# TB-S5D5_p02_Power-v1_2.net
KiCad netlist of a schematic drawn in Altium Designer
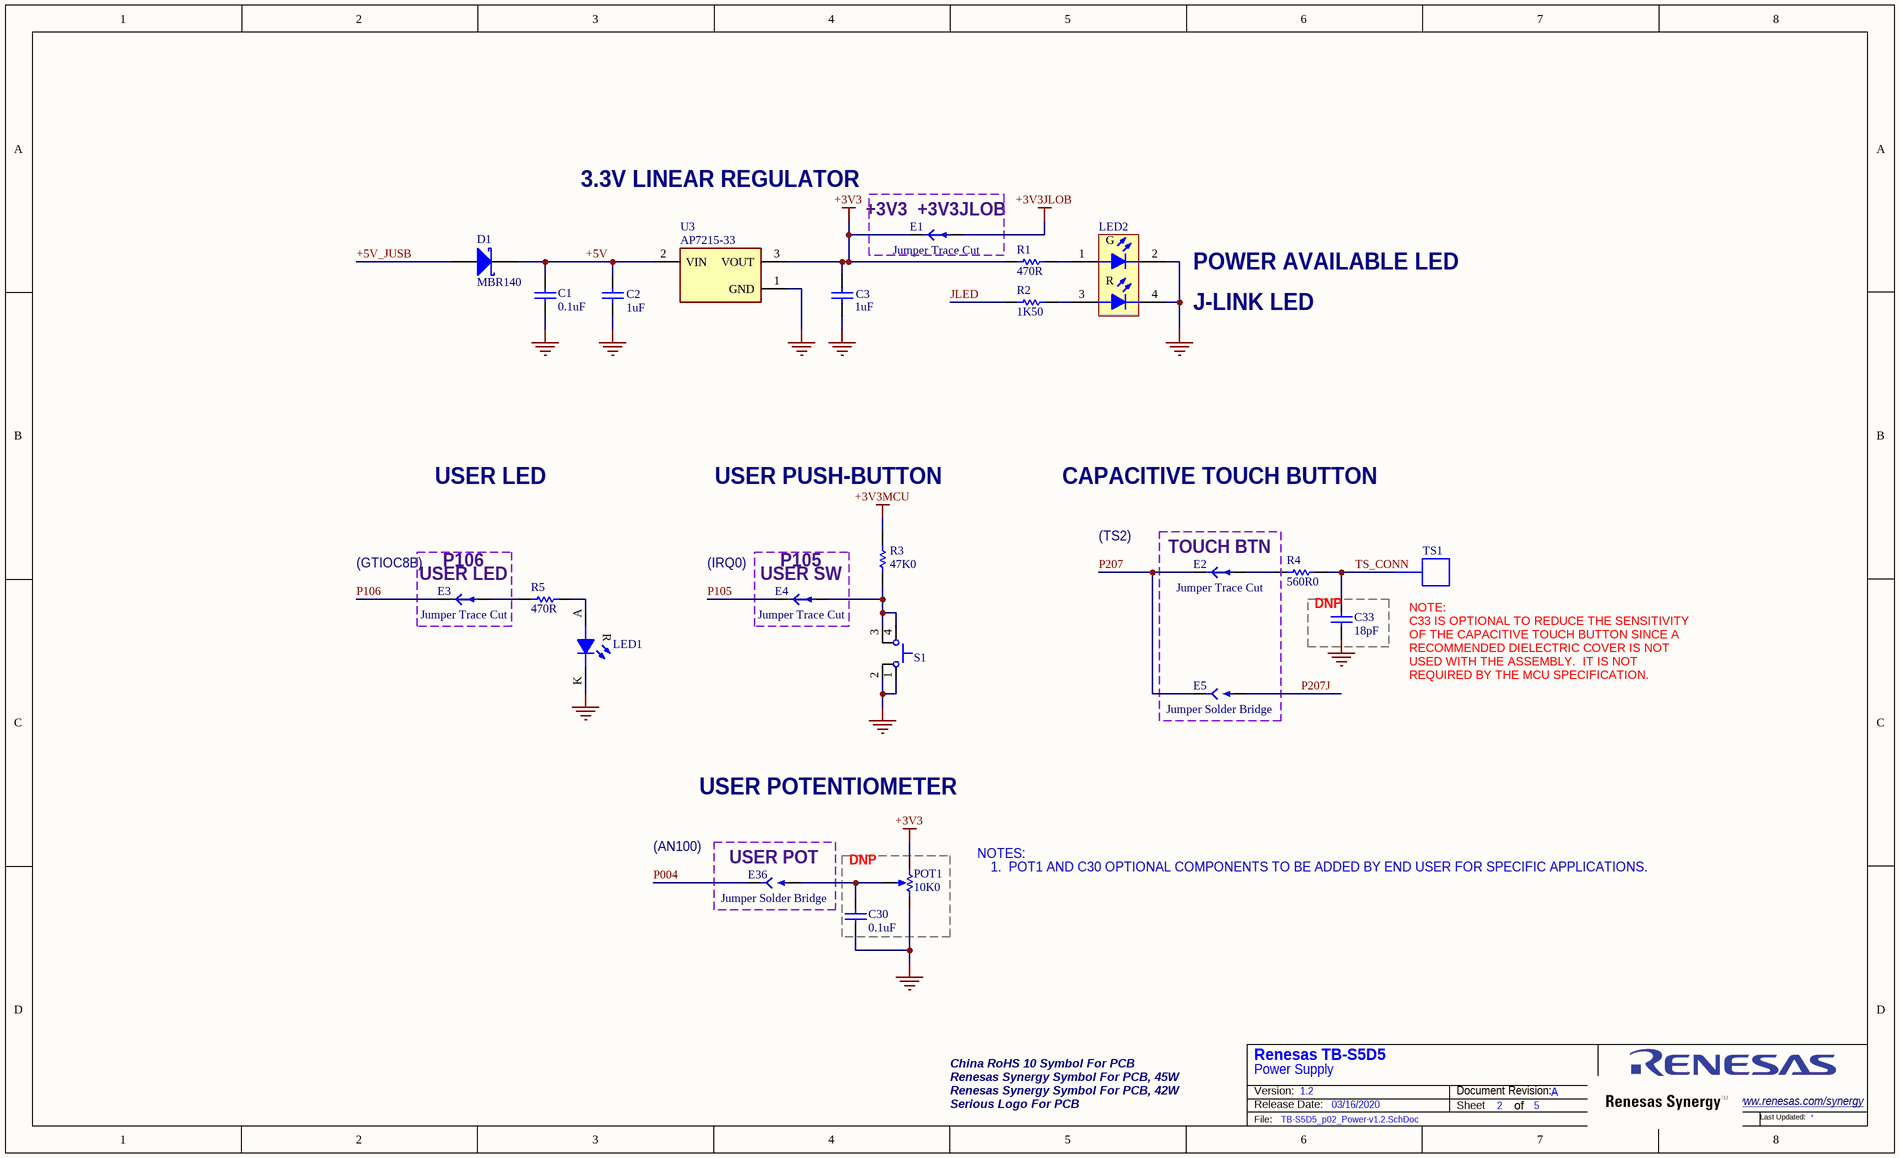
[diagram p0: TB-S5D5_p02_Power-v1.2.SchDoc]

(export (version "E")
  (design (tool "Eeschema 10.0.6"))
  (components
    (comp (ref "A_Logo1")
      (value "This BOM is for Engineering Use Only, NOT FOR PURCHASE USE.")
      (footprint "_SeriousEngineering")
      (description "Combination disclaimer and Serious Integrated Design splash")
      (fields (field (name "MFG PART NUMBER") "(none)"))
      (libsource (lib "SpecialPartsLib") (part "A_Serious_Engineering_Logo"))
    )
    (comp (ref "A_Symbol1")
      (value "This Symbol Placed on PCB only.")
      (footprint "ChinaRoHS-7mm")
      (description "China RoHs Symbol Circle-7")
      (libsource (lib "SpecialPartsLib") (part "A_Symbol_ChinaRoHS07"))
    )
    (comp (ref "A_Symbol2")
      (value "This Symbol Placed on PCB only.")
      (footprint "RenesasSynergyLogo45x7")
      (description "Renesas Synergy Logo, Std 45Wx7.4Hmm")
      (libsource (lib "SpecialPartsLib") (part "A_Symbol_RenesasSynergy-45x7"))
    )
    (comp (ref "A_Symbol3")
      (value "This Symbol Placed on PCB only.")
      (footprint "RenesasSynergyLogo42x7")
      (description "Renesas Synergy Logo, 42Wx6.8Hmm")
      (libsource (lib "SpecialPartsLib") (part "A_Symbol_RenesasSynergy-42x7"))
    )
    (comp (ref "C1")
      (value "CAP-000029-01")
      (footprint "CAPC0603-01")
      (description "Ceramic Chip Capacitor 0603 0.1uF 50V")
      (fields
        (field (name "MANUFACTURER") "Samsung")
        (field (name "MFG PART NUMBER") "CL10B104KB8NNNC")
        (field (name "CAPACITANCE") "0.1uF")
      )
      (libsource (lib "Capacitors") (part "CAP-000029-01"))
    )
    (comp (ref "C2")
      (value "CAP-000063-01")
      (footprint "CAPC0402-01")
      (description "Ceramic Chip Capacitor 0402 1uF 16V")
      (fields
        (field (name "MANUFACTURER") "Samsung")
        (field (name "MFG PART NUMBER") "CL05A105KO5NNNC")
        (field (name "CAPACITANCE") "1uF")
      )
      (libsource (lib "Capacitors") (part "CAP-000063-01"))
    )
    (comp (ref "C3")
      (value "CAP-000063-01")
      (footprint "CAPC0402-01")
      (description "Ceramic Chip Capacitor 0402 1uF 16V")
      (fields
        (field (name "MANUFACTURER") "Samsung")
        (field (name "MFG PART NUMBER") "CL05A105KO5NNNC")
        (field (name "CAPACITANCE") "1uF")
      )
      (libsource (lib "Capacitors") (part "CAP-000063-01"))
    )
    (comp (ref "C30")
      (value "CAP-000029-01")
      (footprint "CAPC0603-01")
      (description "Ceramic Chip Capacitor 0603 0.1uF 50V")
      (fields
        (field (name "MANUFACTURER") "Samsung")
        (field (name "MFG PART NUMBER") "CL10B104KB8NNNC")
        (field (name "CAPACITANCE") "0.1uF")
      )
      (libsource (lib "Capacitors") (part "CAP-000029-01"))
    )
    (comp (ref "C33")
      (value "CAP-000040-01")
      (footprint "CAPC0603-01")
      (description "Ceramic Chip Capacitor 0603 18pF 50V")
      (fields
        (field (name "MANUFACTURER") "Samsung")
        (field (name "MFG PART NUMBER") "CL10C180JB8NNNC")
        (field (name "CAPACITANCE") "18pF")
      )
      (libsource (lib "Capacitors") (part "CAP-000040-01"))
    )
    (comp (ref "D1")
      (value "DIO-000012-01")
      (footprint "ONSEMI_SOD-123LF")
      (description "OnSemi Schottky Power Rectifier 40V 1A")
      (fields
        (field (name "MANUFACTURER") "OnSemi")
        (field (name "VOLTAGE") "40V")
        (field (name "DISPLAY NAME") "MBR140")
      )
      (libsource (lib "Semiconductors") (part "DIO-000012-01"))
    )
    (comp (ref "E1")
      (value "Jumper Trace Cut")
      (footprint "E_PadsTraceCut0805")
      (description "Pads on PCB with Trace Between for Cutting to isolate")
      (libsource (lib "TB_SpecialLib") (part "E_JmpTraceCut"))
    )
    (comp (ref "E2")
      (value "Jumper Trace Cut")
      (footprint "E_PadsTraceCut0805")
      (description "Pads on PCB with Trace Between for Cutting to isolate")
      (libsource (lib "TB_SpecialLib") (part "E_JmpTraceCut"))
    )
    (comp (ref "E3")
      (value "Jumper Trace Cut")
      (footprint "E_PadsTraceCut0805")
      (description "Pads on PCB with Trace Between for Cutting to isolate")
      (libsource (lib "TB_SpecialLib") (part "E_JmpTraceCut"))
    )
    (comp (ref "E4")
      (value "Jumper Trace Cut")
      (footprint "E_PadsTraceCut0805")
      (description "Pads on PCB with Trace Between for Cutting to isolate")
      (libsource (lib "TB_SpecialLib") (part "E_JmpTraceCut"))
    )
    (comp (ref "E5")
      (value "Jumper Solder Bridge")
      (footprint "E_PadsSplit0805")
      (description "Pads on PCB with Narrow Gap to allow Solder Bridging")
      (libsource (lib "TB_SpecialLib") (part "E_JmpSldrBridge"))
    )
    (comp (ref "E36")
      (value "Jumper Solder Bridge")
      (footprint "E_PadsSplit0805")
      (description "Pads on PCB with Narrow Gap to allow Solder Bridging")
      (libsource (lib "TB_SpecialLib") (part "E_JmpSldrBridge"))
    )
    (comp (ref "LED1")
      (value "LED-000005-01")
      (footprint "LED_0603-RED")
      (description "Lite-On LED Red Clear 0603")
      (fields (field (name "MANUFACTURER") "Lite-On") (field (name "MFG PART NUMBER") "LTST-C191KRKT"))
      (libsource (lib "Semiconductors") (part "LED-000005-01"))
    )
    (comp (ref "LED2")
      (value "LED-000001-01")
      (footprint "LED_DIALIGHT-598-8610")
      (description "Dialight Bicolor LED Red/Green 1210")
      (fields (field (name "MANUFACTURER") "Dialight") (field (name "MFG PART NUMBER") "598-8610-207F"))
      (libsource (lib "Semiconductors") (part "LED-000001-01"))
    )
    (comp (ref "POT1")
      (value "POT-000001-02")
      (footprint "BOURNS_3352T")
      (description "Bourns Single Turn Trimmer 10K0")
      (fields
        (field (name "MFG PART NUMBER") "3352T-1-103LF")
        (field (name "TOLERANCE") "20%")
        (field (name "RESISTANCE") "10K0")
      )
      (libsource (lib "Misc") (part "POT-000001-02"))
    )
    (comp (ref "R1")
      (value "RES-000124-01")
      (footprint "RESC0402-01")
      (description "Chip Resistor Thick Film 0402 470R 0.5% 1/16W")
      (fields
        (field (name "MANUFACTURER") "Panasonic")
        (field (name "MFG PART NUMBER") "ERA-2AED471X")
        (field (name "RESISTANCE") "470R")
      )
      (libsource (lib "Resistors") (part "RES-000124-01"))
    )
    (comp (ref "R2")
      (value "RES-000140-01")
      (footprint "RESC0402-01")
      (description "Chip Resistor Thick Film 0402 1K50 0.5% 1/16W")
      (fields
        (field (name "MANUFACTURER") "Panasonic")
        (field (name "MFG PART NUMBER") "ERA-2AED152X")
        (field (name "RESISTANCE") "1K50")
      )
      (libsource (lib "Resistors") (part "RES-000140-01"))
    )
    (comp (ref "R3")
      (value "RES-000173-01")
      (footprint "RESC0402-01")
      (description "Chip Resistor Thick Film 0402 47K0 1% 1/10W")
      (fields
        (field (name "MANUFACTURER") "Panasonic")
        (field (name "MFG PART NUMBER") "ERJ-2RKF4702X")
        (field (name "RESISTANCE") "47K0")
      )
      (libsource (lib "Resistors") (part "RES-000173-01"))
    )
    (comp (ref "R4")
      (value "RES-000206-01")
      (footprint "RESC0603-01")
      (description "Chip Resistor Thick Film 0603 560R0 1% 1/10W")
      (fields
        (field (name "MANUFACTURER") "Panasonic")
        (field (name "MFG PART NUMBER") "ERJ-3EKF5600V")
        (field (name "RESISTANCE") "560R0")
      )
      (libsource (lib "Resistors") (part "RES-000206-01"))
    )
    (comp (ref "R5")
      (value "RES-000124-01")
      (footprint "RESC0402-01")
      (description "Chip Resistor Thick Film 0402 470R 0.5% 1/16W")
      (fields
        (field (name "MANUFACTURER") "Panasonic")
        (field (name "MFG PART NUMBER") "ERA-2AED471X")
        (field (name "RESISTANCE") "470R")
      )
      (libsource (lib "Resistors") (part "RES-000124-01"))
    )
    (comp (ref "S1")
      (value "SWT-000013-01")
      (footprint "SW_C&K_PTS645_43")
      (description "Push Button Switch 6 x 6mm 4.3mm High")
      (fields (field (name "MANUFACTURER") "C&K") (field (name "MFG PART NUMBER") "PTS645SM43SMTR92 LFS"))
      (libsource (lib "Misc") (part "SWT-000013-01"))
    )
    (comp (ref "TS1")
      (value "TOUCH_PAD_OL")
      (footprint "RENESAS_TSP_OL")
      (description "Renesas Touch Sense Pad Outline (for non-Pad use)")
      (libsource (lib "SpecialPartsLib") (part "TOUCH_PAD_OL"))
    )
    (comp (ref "U3")
      (value "ICN-000215-01")
      (footprint "SOT-89-3")
      (description "LDO Regulator 3.3V 600mA")
      (fields
        (field (name "MANUFACTURER") "Diodes")
        (field (name "MFG PART NUMBER") "AP7215-33YG-13")
        (field (name "DISPLAY NAME") "AP7215-33")
      )
      (libsource (lib "IC_Power") (part "ICN-000215-01"))
    )
  )
  (nets
    (net (code "1") (name "+3V3") (class "Default")
      (node (ref "C3") (pin "2") (pinfunction "2_2") (pintype "passive"))
      (node (ref "E1") (pin "1") (pinfunction "A_1") (pintype "passive"))
      (node (ref "POT1") (pin "1") (pinfunction "1_1") (pintype "passive"))
      (node (ref "R1") (pin "1") (pinfunction "1_1") (pintype "passive"))
      (node (ref "U3") (pin "3") (pinfunction "VOUT_3") (pintype "power_in"))
    )
    (net (code "2") (name "+3V3JLOB") (class "Default")
      (node (ref "E1") (pin "2") (pinfunction "A_2") (pintype "passive"))
    )
    (net (code "3") (name "+3V3MCU") (class "Default")
      (node (ref "R3") (pin "2") (pinfunction "2_2") (pintype "passive"))
    )
    (net (code "4") (name "/+5V") (class "Default")
      (node (ref "C1") (pin "2") (pinfunction "2_2") (pintype "passive"))
      (node (ref "C2") (pin "2") (pinfunction "2_2") (pintype "passive"))
      (node (ref "D1") (pin "K") (pinfunction "K_K") (pintype "passive"))
      (node (ref "U3") (pin "2") (pinfunction "VIN_2") (pintype "power_in"))
    )
    (net (code "5") (name "/+5V_JUSB") (class "Default")
      (node (ref "D1") (pin "A") (pinfunction "A_A") (pintype "passive"))
    )
    (net (code "6") (name "/JLED") (class "Default")
      (node (ref "R2") (pin "1") (pinfunction "1_1") (pintype "passive"))
    )
    (net (code "7") (name "/P004") (class "Default")
      (node (ref "E36") (pin "1") (pinfunction "A_1") (pintype "passive"))
    )
    (net (code "8") (name "/P105") (class "Default")
      (node (ref "E4") (pin "1") (pinfunction "A_1") (pintype "passive"))
    )
    (net (code "9") (name "/P106") (class "Default")
      (node (ref "E3") (pin "1") (pinfunction "A_1") (pintype "passive"))
    )
    (net (code "10") (name "/P207") (class "Default")
      (node (ref "E2") (pin "1") (pinfunction "A_1") (pintype "passive"))
      (node (ref "E5") (pin "1") (pinfunction "A_1") (pintype "passive"))
    )
    (net (code "11") (name "/P207J") (class "Default")
      (node (ref "E5") (pin "2") (pinfunction "A_2") (pintype "passive"))
    )
    (net (code "12") (name "/TS_CONN") (class "Default")
      (node (ref "C33") (pin "2") (pinfunction "2_2") (pintype "passive"))
      (node (ref "R4") (pin "2") (pinfunction "2_2") (pintype "passive"))
    )
    (net (code "13") (name "GND") (class "Default")
      (node (ref "C1") (pin "1") (pinfunction "1_1") (pintype "passive"))
      (node (ref "C2") (pin "1") (pinfunction "1_1") (pintype "passive"))
      (node (ref "C3") (pin "1") (pinfunction "1_1") (pintype "passive"))
      (node (ref "C30") (pin "1") (pinfunction "1_1") (pintype "passive"))
      (node (ref "C33") (pin "1") (pinfunction "1_1") (pintype "passive"))
      (node (ref "LED1") (pin "K") (pinfunction "K_K") (pintype "passive"))
      (node (ref "LED2") (pin "2") (pinfunction "K1_2") (pintype "passive"))
      (node (ref "LED2") (pin "4") (pinfunction "K2_4") (pintype "passive"))
      (node (ref "POT1") (pin "3") (pinfunction "3_3") (pintype "passive"))
      (node (ref "S1") (pin "1") (pinfunction "1_1") (pintype "passive"))
      (node (ref "S1") (pin "2") (pinfunction "2_2") (pintype "passive"))
      (node (ref "U3") (pin "1") (pinfunction "GND_1") (pintype "power_in"))
    )
    (net (code "14") (name "Net-(C30-Pad2)") (class "Default")
      (node (ref "C30") (pin "2") (pinfunction "2_2") (pintype "passive"))
      (node (ref "E36") (pin "2") (pinfunction "A_2") (pintype "passive"))
      (node (ref "POT1") (pin "2") (pinfunction "2_2") (pintype "passive"))
    )
    (net (code "15") (name "Net-(E2-A-Pad2)") (class "Default")
      (node (ref "E2") (pin "2") (pinfunction "A_2") (pintype "passive"))
      (node (ref "R4") (pin "1") (pinfunction "1_1") (pintype "passive"))
    )
    (net (code "16") (name "Net-(E3-A-Pad2)") (class "Default")
      (node (ref "E3") (pin "2") (pinfunction "A_2") (pintype "passive"))
      (node (ref "R5") (pin "2") (pinfunction "2_2") (pintype "passive"))
    )
    (net (code "17") (name "Net-(E4-A-Pad2)") (class "Default")
      (node (ref "E4") (pin "2") (pinfunction "A_2") (pintype "passive"))
      (node (ref "R3") (pin "1") (pinfunction "1_1") (pintype "passive"))
      (node (ref "S1") (pin "3") (pinfunction "3_3") (pintype "passive"))
      (node (ref "S1") (pin "4") (pinfunction "4_4") (pintype "passive"))
    )
    (net (code "18") (name "Net-(LED1-PadA)") (class "Default")
      (node (ref "LED1") (pin "A") (pinfunction "A_A") (pintype "passive"))
      (node (ref "R5") (pin "1") (pinfunction "1_1") (pintype "passive"))
    )
    (net (code "19") (name "Net-(LED2-A1)") (class "Default")
      (node (ref "LED2") (pin "1") (pinfunction "A1_1") (pintype "passive"))
      (node (ref "R1") (pin "2") (pinfunction "2_2") (pintype "passive"))
    )
    (net (code "20") (name "Net-(LED2-A2)") (class "Default")
      (node (ref "LED2") (pin "3") (pinfunction "A2_3") (pintype "passive"))
      (node (ref "R2") (pin "2") (pinfunction "2_2") (pintype "passive"))
    )
  )
)
